# CONTROL-SWITCHES.net
KiCad netlist of a schematic drawn in Altium Designer
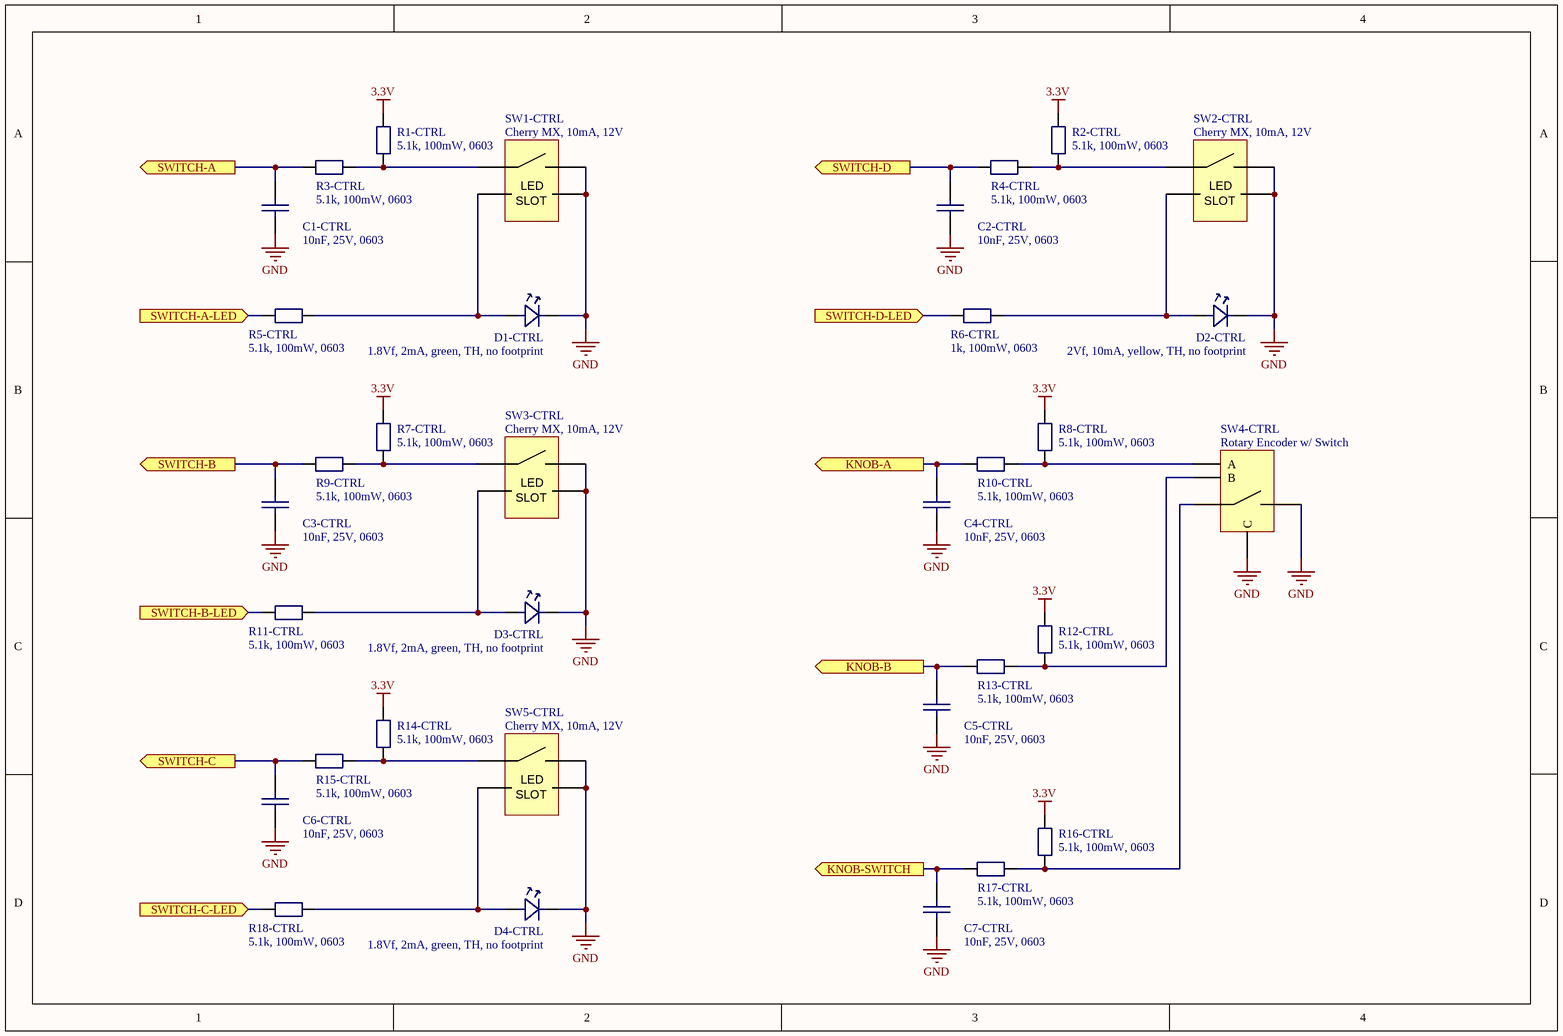
[diagram p0: CONTROL-SWITCHES.SchDoc]

(export (version "E")
  (design (tool "Eeschema 10.0.6"))
  (components
    (comp (ref "C1-CTRL")
      (value "10nF, 25V, 0603")
      (footprint "0603 [1608]")
      (fields (field (name "MANUFACTURER") "YAGEO"))
      (libsource (lib "SCH-LIB") (part "Capacitor"))
    )
    (comp (ref "C2-CTRL")
      (value "10nF, 25V, 0603")
      (footprint "0603 [1608]")
      (fields (field (name "MANUFACTURER") "YAGEO"))
      (libsource (lib "SCH-LIB") (part "Capacitor"))
    )
    (comp (ref "C3-CTRL")
      (value "10nF, 25V, 0603")
      (footprint "0603 [1608]")
      (fields (field (name "MANUFACTURER") "YAGEO"))
      (libsource (lib "SCH-LIB") (part "Capacitor"))
    )
    (comp (ref "C4-CTRL")
      (value "10nF, 25V, 0603")
      (footprint "0603 [1608]")
      (fields (field (name "MANUFACTURER") "YAGEO"))
      (libsource (lib "SCH-LIB") (part "Capacitor"))
    )
    (comp (ref "C5-CTRL")
      (value "10nF, 25V, 0603")
      (footprint "0603 [1608]")
      (fields (field (name "MANUFACTURER") "YAGEO"))
      (libsource (lib "SCH-LIB") (part "Capacitor"))
    )
    (comp (ref "C6-CTRL")
      (value "10nF, 25V, 0603")
      (footprint "0603 [1608]")
      (fields (field (name "MANUFACTURER") "YAGEO"))
      (libsource (lib "SCH-LIB") (part "Capacitor"))
    )
    (comp (ref "C7-CTRL")
      (value "10nF, 25V, 0603")
      (footprint "0603 [1608]")
      (fields (field (name "MANUFACTURER") "YAGEO"))
      (libsource (lib "SCH-LIB") (part "Capacitor"))
    )
    (comp (ref "D1-CTRL")
      (value "1.8Vf, 2mA, green, TH, no footprint")
      (footprint "LED 0603 [1608]")
      (fields (field (name "MANUFACTURER") "MULTICOMP PRO"))
      (libsource (lib "SCH-LIB") (part "LED"))
    )
    (comp (ref "D2-CTRL")
      (value "2Vf, 10mA, yellow, TH, no footprint")
      (footprint "LED 0603 [1608]")
      (fields (field (name "MANUFACTURER") "BROADCOM"))
      (libsource (lib "SCH-LIB") (part "LED"))
    )
    (comp (ref "D3-CTRL")
      (value "1.8Vf, 2mA, green, TH, no footprint")
      (footprint "LED 0603 [1608]")
      (fields (field (name "MANUFACTURER") "MULTICOMP PRO"))
      (libsource (lib "SCH-LIB") (part "LED"))
    )
    (comp (ref "D4-CTRL")
      (value "1.8Vf, 2mA, green, TH, no footprint")
      (footprint "LED 0603 [1608]")
      (fields (field (name "MANUFACTURER") "MULTICOMP PRO"))
      (libsource (lib "SCH-LIB") (part "LED"))
    )
    (comp (ref "R1-CTRL")
      (value "5.1k, 100mW, 0603")
      (footprint "0603 [1608]")
      (fields (field (name "MANUFACTURER") "YAGEO"))
      (libsource (lib "SCH-LIB") (part "Resistor"))
    )
    (comp (ref "R2-CTRL")
      (value "5.1k, 100mW, 0603")
      (footprint "0603 [1608]")
      (fields (field (name "MANUFACTURER") "YAGEO"))
      (libsource (lib "SCH-LIB") (part "Resistor"))
    )
    (comp (ref "R3-CTRL")
      (value "5.1k, 100mW, 0603")
      (footprint "0603 [1608]")
      (fields (field (name "MANUFACTURER") "YAGEO"))
      (libsource (lib "SCH-LIB") (part "Resistor"))
    )
    (comp (ref "R4-CTRL")
      (value "5.1k, 100mW, 0603")
      (footprint "0603 [1608]")
      (fields (field (name "MANUFACTURER") "YAGEO"))
      (libsource (lib "SCH-LIB") (part "Resistor"))
    )
    (comp (ref "R5-CTRL")
      (value "5.1k, 100mW, 0603")
      (footprint "0603 [1608]")
      (fields (field (name "MANUFACTURER") "YAGEO"))
      (libsource (lib "SCH-LIB") (part "Resistor"))
    )
    (comp (ref "R6-CTRL")
      (value "1k, 100mW, 0603")
      (footprint "0603 [1608]")
      (fields (field (name "MANUFACTURER") "KOA"))
      (libsource (lib "SCH-LIB") (part "Resistor"))
    )
    (comp (ref "R7-CTRL")
      (value "5.1k, 100mW, 0603")
      (footprint "0603 [1608]")
      (fields (field (name "MANUFACTURER") "YAGEO"))
      (libsource (lib "SCH-LIB") (part "Resistor"))
    )
    (comp (ref "R8-CTRL")
      (value "5.1k, 100mW, 0603")
      (footprint "0603 [1608]")
      (fields (field (name "MANUFACTURER") "YAGEO"))
      (libsource (lib "SCH-LIB") (part "Resistor"))
    )
    (comp (ref "R9-CTRL")
      (value "5.1k, 100mW, 0603")
      (footprint "0603 [1608]")
      (fields (field (name "MANUFACTURER") "YAGEO"))
      (libsource (lib "SCH-LIB") (part "Resistor"))
    )
    (comp (ref "R10-CTRL")
      (value "5.1k, 100mW, 0603")
      (footprint "0603 [1608]")
      (fields (field (name "MANUFACTURER") "YAGEO"))
      (libsource (lib "SCH-LIB") (part "Resistor"))
    )
    (comp (ref "R11-CTRL")
      (value "5.1k, 100mW, 0603")
      (footprint "0603 [1608]")
      (fields (field (name "MANUFACTURER") "YAGEO"))
      (libsource (lib "SCH-LIB") (part "Resistor"))
    )
    (comp (ref "R12-CTRL")
      (value "5.1k, 100mW, 0603")
      (footprint "0603 [1608]")
      (fields (field (name "MANUFACTURER") "YAGEO"))
      (libsource (lib "SCH-LIB") (part "Resistor"))
    )
    (comp (ref "R13-CTRL")
      (value "5.1k, 100mW, 0603")
      (footprint "0603 [1608]")
      (fields (field (name "MANUFACTURER") "YAGEO"))
      (libsource (lib "SCH-LIB") (part "Resistor"))
    )
    (comp (ref "R14-CTRL")
      (value "5.1k, 100mW, 0603")
      (footprint "0603 [1608]")
      (fields (field (name "MANUFACTURER") "YAGEO"))
      (libsource (lib "SCH-LIB") (part "Resistor"))
    )
    (comp (ref "R15-CTRL")
      (value "5.1k, 100mW, 0603")
      (footprint "0603 [1608]")
      (fields (field (name "MANUFACTURER") "YAGEO"))
      (libsource (lib "SCH-LIB") (part "Resistor"))
    )
    (comp (ref "R16-CTRL")
      (value "5.1k, 100mW, 0603")
      (footprint "0603 [1608]")
      (fields (field (name "MANUFACTURER") "YAGEO"))
      (libsource (lib "SCH-LIB") (part "Resistor"))
    )
    (comp (ref "R17-CTRL")
      (value "5.1k, 100mW, 0603")
      (footprint "0603 [1608]")
      (fields (field (name "MANUFACTURER") "YAGEO"))
      (libsource (lib "SCH-LIB") (part "Resistor"))
    )
    (comp (ref "R18-CTRL")
      (value "5.1k, 100mW, 0603")
      (footprint "0603 [1608]")
      (fields (field (name "MANUFACTURER") "YAGEO"))
      (libsource (lib "SCH-LIB") (part "Resistor"))
    )
    (comp (ref "SW1-CTRL")
      (value "Cherry MX, 10mA, 12V")
      (footprint "Cherry MX Switch")
      (fields (field (name "MANUFACTURER") "Cherry Americas LLC"))
      (libsource (lib "SCH-LIB") (part "Cherry MX Switch"))
    )
    (comp (ref "SW2-CTRL")
      (value "Cherry MX, 10mA, 12V")
      (footprint "Cherry MX Switch")
      (fields (field (name "MANUFACTURER") "Cherry Americas LLC"))
      (libsource (lib "SCH-LIB") (part "Cherry MX Switch"))
    )
    (comp (ref "SW3-CTRL")
      (value "Cherry MX, 10mA, 12V")
      (footprint "Cherry MX Switch")
      (fields (field (name "MANUFACTURER") "Cherry Americas LLC"))
      (libsource (lib "SCH-LIB") (part "Cherry MX Switch"))
    )
    (comp (ref "SW4-CTRL")
      (value "Rotary Encoder w/ Switch")
      (footprint "Rotary Encoder w/ Switch (Bourns)")
      (fields (field (name "MANUFACTURER") "Bourns"))
      (libsource (lib "SCH-LIB") (part "Rotary Encoder w/ Switch"))
    )
    (comp (ref "SW5-CTRL")
      (value "Cherry MX, 10mA, 12V")
      (footprint "Cherry MX Switch")
      (fields (field (name "MANUFACTURER") "Cherry Americas LLC"))
      (libsource (lib "SCH-LIB") (part "Cherry MX Switch"))
    )
  )
  (nets
    (net (code "1") (name "/KNOB-A") (class "Default")
      (node (ref "C4-CTRL") (pin "2") (pinfunction "2_2") (pintype "passive"))
      (node (ref "R10-CTRL") (pin "2") (pinfunction "2_2") (pintype "passive"))
    )
    (net (code "2") (name "/KNOB-B") (class "Default")
      (node (ref "C5-CTRL") (pin "2") (pinfunction "2_2") (pintype "passive"))
      (node (ref "R13-CTRL") (pin "2") (pinfunction "2_2") (pintype "passive"))
    )
    (net (code "3") (name "/KNOB-SWITCH") (class "Default")
      (node (ref "C7-CTRL") (pin "2") (pinfunction "2_2") (pintype "passive"))
      (node (ref "R17-CTRL") (pin "2") (pinfunction "2_2") (pintype "passive"))
    )
    (net (code "4") (name "/SWITCH-A") (class "Default")
      (node (ref "C1-CTRL") (pin "2") (pinfunction "2_2") (pintype "passive"))
      (node (ref "R3-CTRL") (pin "2") (pinfunction "2_2") (pintype "passive"))
    )
    (net (code "5") (name "/SWITCH-A-LED") (class "Default")
      (node (ref "R5-CTRL") (pin "1") (pinfunction "1_1") (pintype "passive"))
    )
    (net (code "6") (name "/SWITCH-B") (class "Default")
      (node (ref "C3-CTRL") (pin "2") (pinfunction "2_2") (pintype "passive"))
      (node (ref "R9-CTRL") (pin "2") (pinfunction "2_2") (pintype "passive"))
    )
    (net (code "7") (name "/SWITCH-B-LED") (class "Default")
      (node (ref "R11-CTRL") (pin "1") (pinfunction "1_1") (pintype "passive"))
    )
    (net (code "8") (name "/SWITCH-C") (class "Default")
      (node (ref "C6-CTRL") (pin "2") (pinfunction "2_2") (pintype "passive"))
      (node (ref "R15-CTRL") (pin "2") (pinfunction "2_2") (pintype "passive"))
    )
    (net (code "9") (name "/SWITCH-C-LED") (class "Default")
      (node (ref "R18-CTRL") (pin "1") (pinfunction "1_1") (pintype "passive"))
    )
    (net (code "10") (name "/SWITCH-D") (class "Default")
      (node (ref "C2-CTRL") (pin "2") (pinfunction "2_2") (pintype "passive"))
      (node (ref "R4-CTRL") (pin "2") (pinfunction "2_2") (pintype "passive"))
    )
    (net (code "11") (name "/SWITCH-D-LED") (class "Default")
      (node (ref "R6-CTRL") (pin "1") (pinfunction "1_1") (pintype "passive"))
    )
    (net (code "12") (name "3.3V") (class "Default")
      (node (ref "R1-CTRL") (pin "2") (pinfunction "2_2") (pintype "passive"))
      (node (ref "R12-CTRL") (pin "2") (pinfunction "2_2") (pintype "passive"))
      (node (ref "R14-CTRL") (pin "2") (pinfunction "2_2") (pintype "passive"))
      (node (ref "R16-CTRL") (pin "2") (pinfunction "2_2") (pintype "passive"))
      (node (ref "R2-CTRL") (pin "2") (pinfunction "2_2") (pintype "passive"))
      (node (ref "R7-CTRL") (pin "2") (pinfunction "2_2") (pintype "passive"))
      (node (ref "R8-CTRL") (pin "2") (pinfunction "2_2") (pintype "passive"))
    )
    (net (code "13") (name "GND") (class "Default")
      (node (ref "C1-CTRL") (pin "1") (pinfunction "1_1") (pintype "passive"))
      (node (ref "C2-CTRL") (pin "1") (pinfunction "1_1") (pintype "passive"))
      (node (ref "C3-CTRL") (pin "1") (pinfunction "1_1") (pintype "passive"))
      (node (ref "C4-CTRL") (pin "1") (pinfunction "1_1") (pintype "passive"))
      (node (ref "C5-CTRL") (pin "1") (pinfunction "1_1") (pintype "passive"))
      (node (ref "C6-CTRL") (pin "1") (pinfunction "1_1") (pintype "passive"))
      (node (ref "C7-CTRL") (pin "1") (pinfunction "1_1") (pintype "passive"))
      (node (ref "D1-CTRL") (pin "1") (pinfunction "1_1") (pintype "passive"))
      (node (ref "D2-CTRL") (pin "1") (pinfunction "1_1") (pintype "passive"))
      (node (ref "D3-CTRL") (pin "1") (pinfunction "1_1") (pintype "passive"))
      (node (ref "D4-CTRL") (pin "1") (pinfunction "1_1") (pintype "passive"))
      (node (ref "SW1-CTRL") (pin "2") (pinfunction "2_2") (pintype "passive"))
      (node (ref "SW1-CTRL") (pin "4") (pinfunction "4_4") (pintype "passive"))
      (node (ref "SW2-CTRL") (pin "2") (pinfunction "2_2") (pintype "passive"))
      (node (ref "SW2-CTRL") (pin "4") (pinfunction "4_4") (pintype "passive"))
      (node (ref "SW3-CTRL") (pin "2") (pinfunction "2_2") (pintype "passive"))
      (node (ref "SW3-CTRL") (pin "4") (pinfunction "4_4") (pintype "passive"))
      (node (ref "SW4-CTRL") (pin "2") (pinfunction "2_2") (pintype "passive"))
      (node (ref "SW4-CTRL") (pin "C") (pinfunction "C_C") (pintype "passive"))
      (node (ref "SW5-CTRL") (pin "2") (pinfunction "2_2") (pintype "passive"))
      (node (ref "SW5-CTRL") (pin "4") (pinfunction "4_4") (pintype "passive"))
    )
    (net (code "14") (name "Net-(D1-CTRL-Pad2)") (class "Default")
      (node (ref "D1-CTRL") (pin "2") (pinfunction "2_2") (pintype "passive"))
      (node (ref "R5-CTRL") (pin "2") (pinfunction "2_2") (pintype "passive"))
      (node (ref "SW1-CTRL") (pin "3") (pinfunction "3_3") (pintype "passive"))
    )
    (net (code "15") (name "Net-(D2-CTRL-Pad2)") (class "Default")
      (node (ref "D2-CTRL") (pin "2") (pinfunction "2_2") (pintype "passive"))
      (node (ref "R6-CTRL") (pin "2") (pinfunction "2_2") (pintype "passive"))
      (node (ref "SW2-CTRL") (pin "3") (pinfunction "3_3") (pintype "passive"))
    )
    (net (code "16") (name "Net-(D3-CTRL-Pad2)") (class "Default")
      (node (ref "D3-CTRL") (pin "2") (pinfunction "2_2") (pintype "passive"))
      (node (ref "R11-CTRL") (pin "2") (pinfunction "2_2") (pintype "passive"))
      (node (ref "SW3-CTRL") (pin "3") (pinfunction "3_3") (pintype "passive"))
    )
    (net (code "17") (name "Net-(D4-CTRL-Pad2)") (class "Default")
      (node (ref "D4-CTRL") (pin "2") (pinfunction "2_2") (pintype "passive"))
      (node (ref "R18-CTRL") (pin "2") (pinfunction "2_2") (pintype "passive"))
      (node (ref "SW5-CTRL") (pin "3") (pinfunction "3_3") (pintype "passive"))
    )
    (net (code "18") (name "Net-(R1-CTRL-Pad1)") (class "Default")
      (node (ref "R1-CTRL") (pin "1") (pinfunction "1_1") (pintype "passive"))
      (node (ref "R3-CTRL") (pin "1") (pinfunction "1_1") (pintype "passive"))
      (node (ref "SW1-CTRL") (pin "1") (pinfunction "1_1") (pintype "passive"))
    )
    (net (code "19") (name "Net-(R2-CTRL-Pad1)") (class "Default")
      (node (ref "R2-CTRL") (pin "1") (pinfunction "1_1") (pintype "passive"))
      (node (ref "R4-CTRL") (pin "1") (pinfunction "1_1") (pintype "passive"))
      (node (ref "SW2-CTRL") (pin "1") (pinfunction "1_1") (pintype "passive"))
    )
    (net (code "20") (name "Net-(R7-CTRL-Pad1)") (class "Default")
      (node (ref "R7-CTRL") (pin "1") (pinfunction "1_1") (pintype "passive"))
      (node (ref "R9-CTRL") (pin "1") (pinfunction "1_1") (pintype "passive"))
      (node (ref "SW3-CTRL") (pin "1") (pinfunction "1_1") (pintype "passive"))
    )
    (net (code "21") (name "Net-(R10-CTRL-Pad1)") (class "Default")
      (node (ref "R10-CTRL") (pin "1") (pinfunction "1_1") (pintype "passive"))
      (node (ref "R8-CTRL") (pin "1") (pinfunction "1_1") (pintype "passive"))
      (node (ref "SW4-CTRL") (pin "A") (pinfunction "A_A") (pintype "passive"))
    )
    (net (code "22") (name "Net-(R12-CTRL-Pad1)") (class "Default")
      (node (ref "R12-CTRL") (pin "1") (pinfunction "1_1") (pintype "passive"))
      (node (ref "R13-CTRL") (pin "1") (pinfunction "1_1") (pintype "passive"))
      (node (ref "SW4-CTRL") (pin "B") (pinfunction "B_B") (pintype "passive"))
    )
    (net (code "23") (name "Net-(R14-CTRL-Pad1)") (class "Default")
      (node (ref "R14-CTRL") (pin "1") (pinfunction "1_1") (pintype "passive"))
      (node (ref "R15-CTRL") (pin "1") (pinfunction "1_1") (pintype "passive"))
      (node (ref "SW5-CTRL") (pin "1") (pinfunction "1_1") (pintype "passive"))
    )
    (net (code "24") (name "Net-(R16-CTRL-Pad1)") (class "Default")
      (node (ref "R16-CTRL") (pin "1") (pinfunction "1_1") (pintype "passive"))
      (node (ref "R17-CTRL") (pin "1") (pinfunction "1_1") (pintype "passive"))
      (node (ref "SW4-CTRL") (pin "1") (pinfunction "1_1") (pintype "passive"))
    )
  )
)
